# SCH_Christmas-Tree-1_2024-12-28.net
KiCad netlist of a schematic drawn in EasyEDA
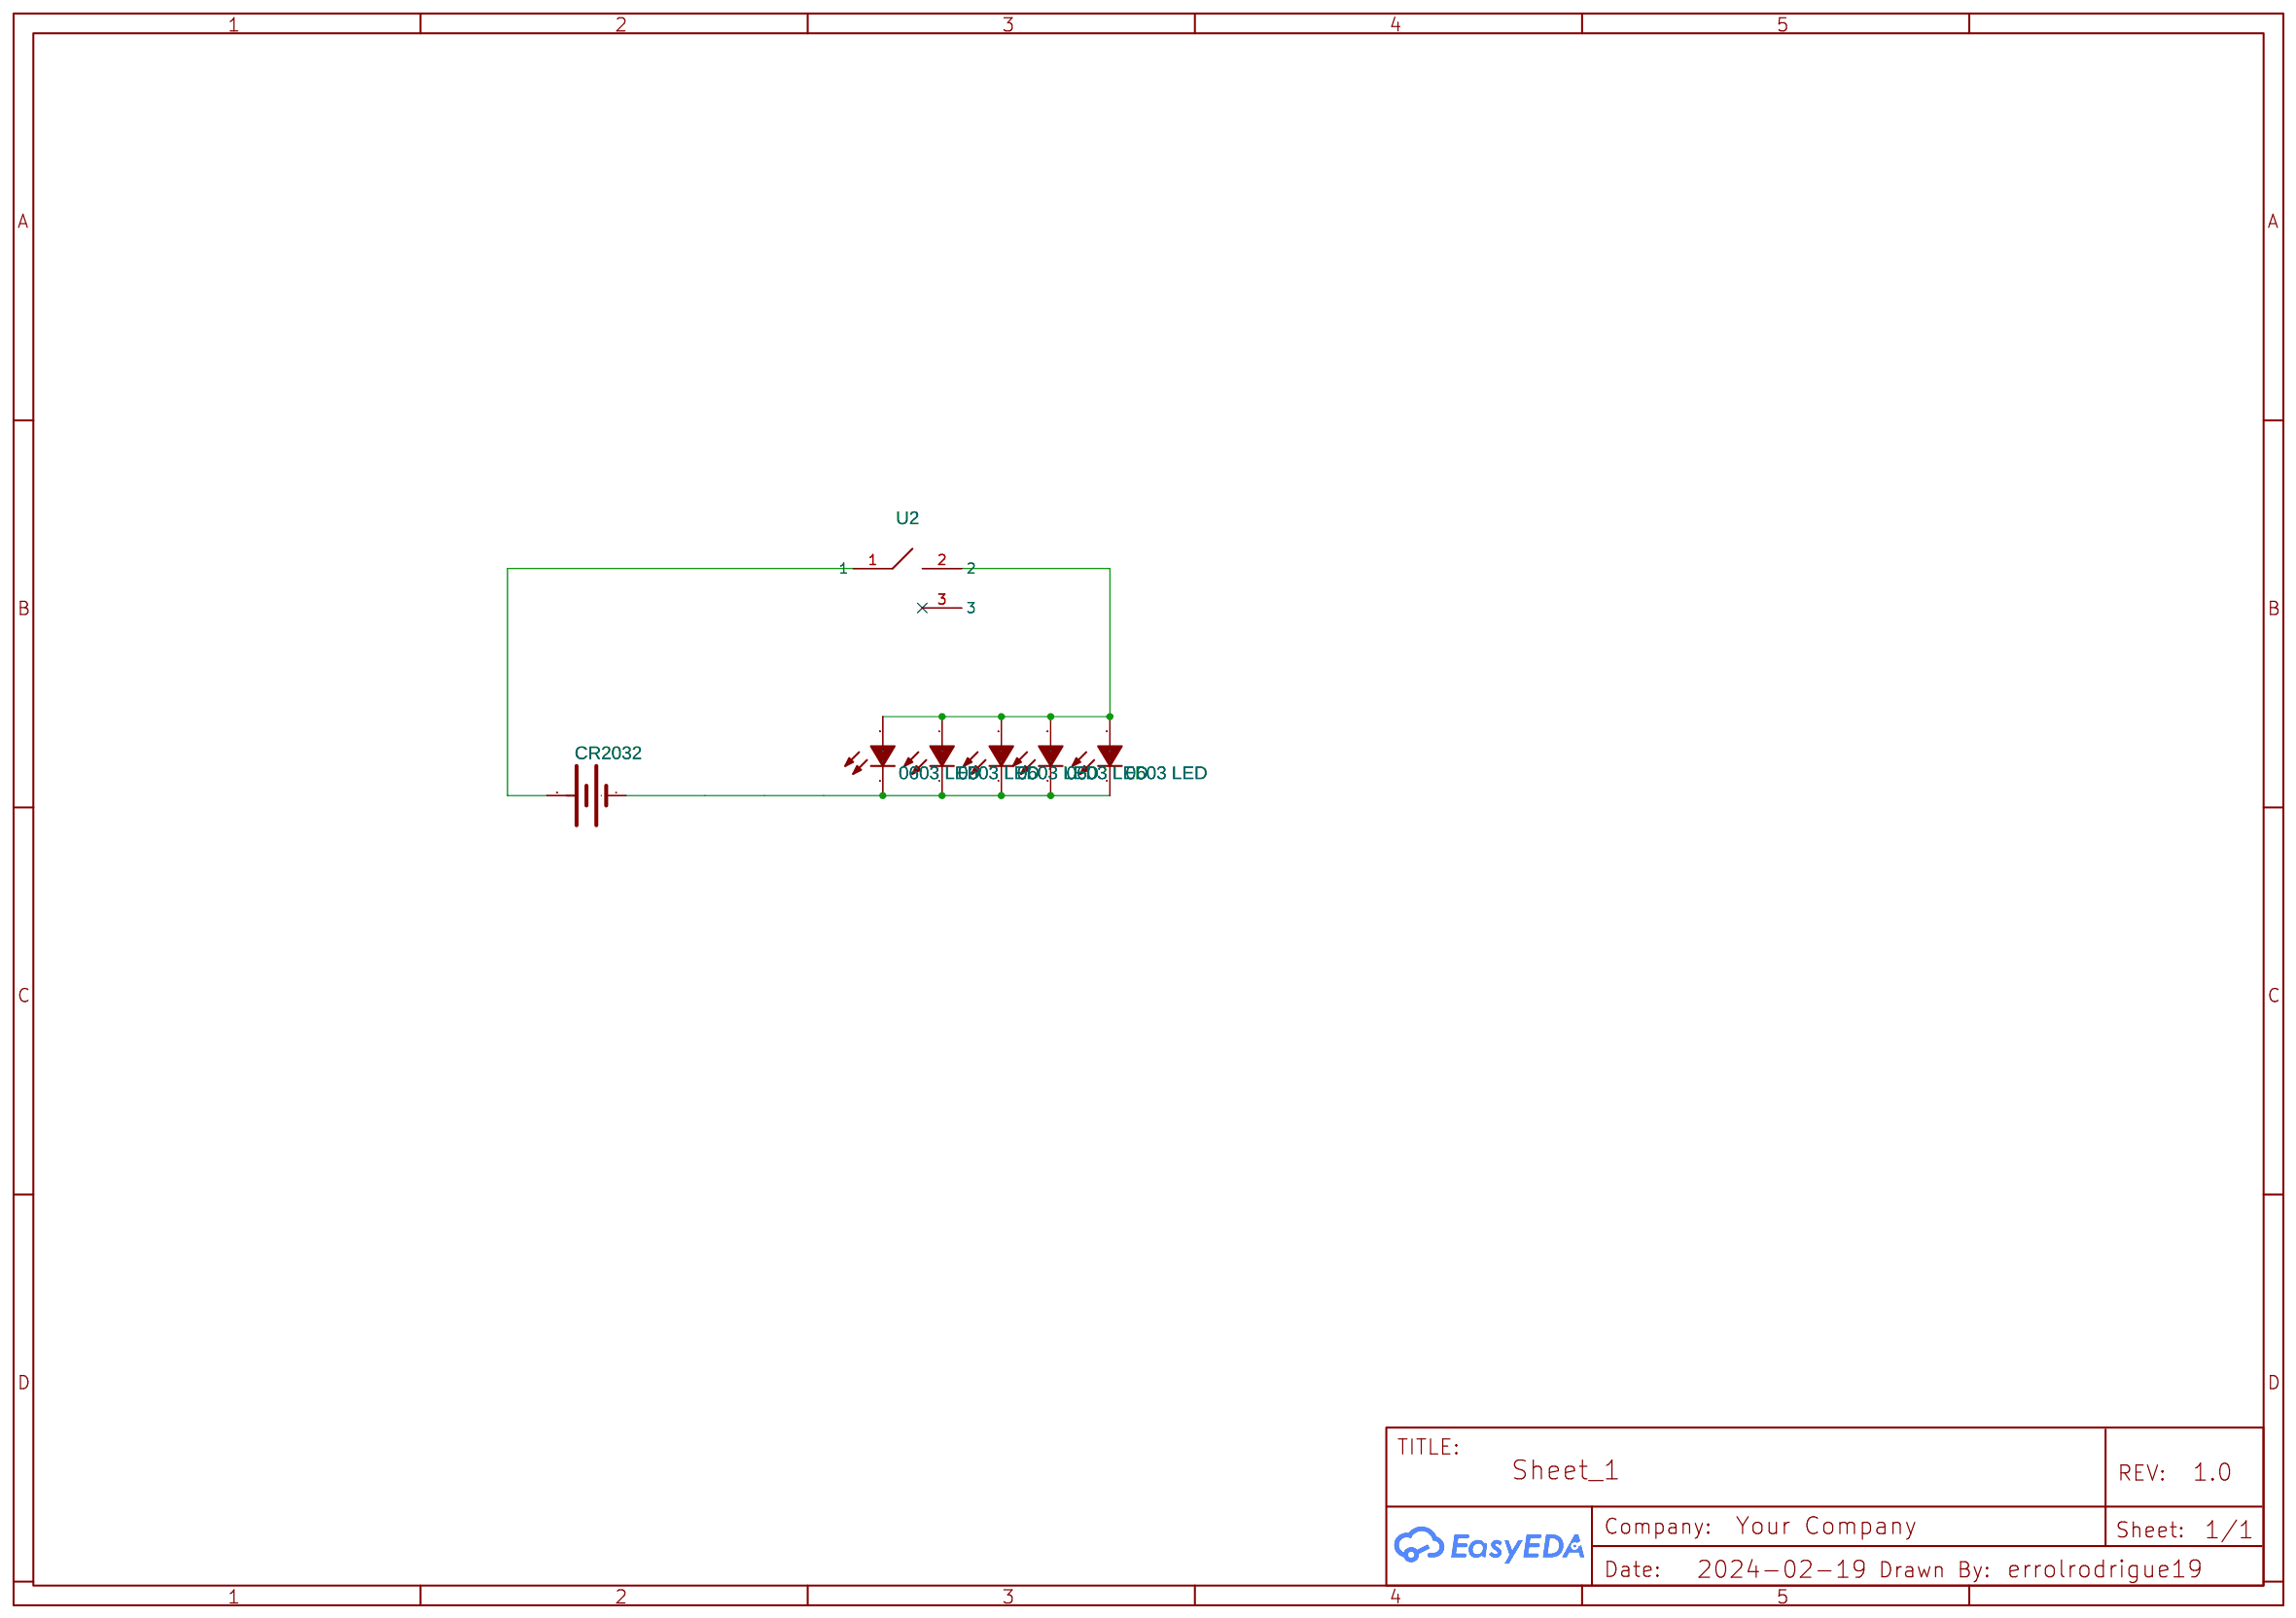
[diagram p0: schematic sheet]

(export (version "E")
  (design (tool "Eeschema 10.0.6"))
  (components
    (comp (ref "LED2")
      (value "0603 LED")
      (fields (field (name "Manufacturer Part") "LED-0603"))
      (libsource (lib "") (part "LED-0603"))
    )
    (comp (ref "LED3")
      (value "0603 LED")
      (fields (field (name "Manufacturer Part") "LED-0603"))
      (libsource (lib "") (part "LED-0603"))
    )
    (comp (ref "LED4")
      (value "0603 LED")
      (fields (field (name "Manufacturer Part") "LED-0603"))
      (libsource (lib "") (part "LED-0603"))
    )
    (comp (ref "LED7")
      (value "0603 LED")
      (fields (field (name "Manufacturer Part") "LED-0603"))
      (libsource (lib "") (part "LED-0603"))
    )
    (comp (ref "LED8")
      (value "0603 LED")
      (fields (field (name "Manufacturer Part") "LED-0603"))
      (libsource (lib "") (part "LED-0603"))
    )
    (comp (ref "U1")
      (value "CR2032")
      (fields (field (name "Manufacturer Part") "CR2032-卧式贴片"))
      (libsource (lib "") (part "CR2032-卧式贴片"))
    )
    (comp (ref "U2") (value "拨键开关MSK-12C02") (libsource (lib "") (part "拨键开关MSK-12C02")))
  )
  (nets
    (net (code "1") (name "Net-(LED2-+)") (class "Default")
      (node (ref "LED2") (pin "2") (pinfunction "+_2") (pintype "input"))
      (node (ref "LED3") (pin "2") (pinfunction "+_2") (pintype "input"))
      (node (ref "LED4") (pin "2") (pinfunction "+_2") (pintype "input"))
      (node (ref "LED7") (pin "2") (pinfunction "+_2") (pintype "input"))
      (node (ref "LED8") (pin "2") (pinfunction "+_2") (pintype "input"))
      (node (ref "U2") (pin "2") (pinfunction "2_2") (pintype "unspecified"))
    )
    (net (code "2") (name "Net-(LED2--)") (class "Default")
      (node (ref "LED2") (pin "1") (pinfunction "-_1") (pintype "input"))
      (node (ref "LED3") (pin "1") (pinfunction "-_1") (pintype "input"))
      (node (ref "LED4") (pin "1") (pinfunction "-_1") (pintype "input"))
      (node (ref "LED7") (pin "1") (pinfunction "-_1") (pintype "input"))
      (node (ref "LED8") (pin "1") (pinfunction "-_1") (pintype "input"))
      (node (ref "U1") (pin "1") (pinfunction "-_1") (pintype "passive"))
    )
    (net (code "3") (name "Net-(U1-+)") (class "Default")
      (node (ref "U1") (pin "2") (pinfunction "+_2") (pintype "passive"))
      (node (ref "U2") (pin "1") (pinfunction "1_1") (pintype "unspecified"))
    )
    (net (code "4") (name "unconnected-(U2-Pad3)") (class "Default")
      (node (ref "U2") (pin "3") (pinfunction "3_3") (pintype "unspecified+no_connect"))
    )
  )
)
